# GSM.net
KiCad netlist of a schematic drawn in Altium Designer
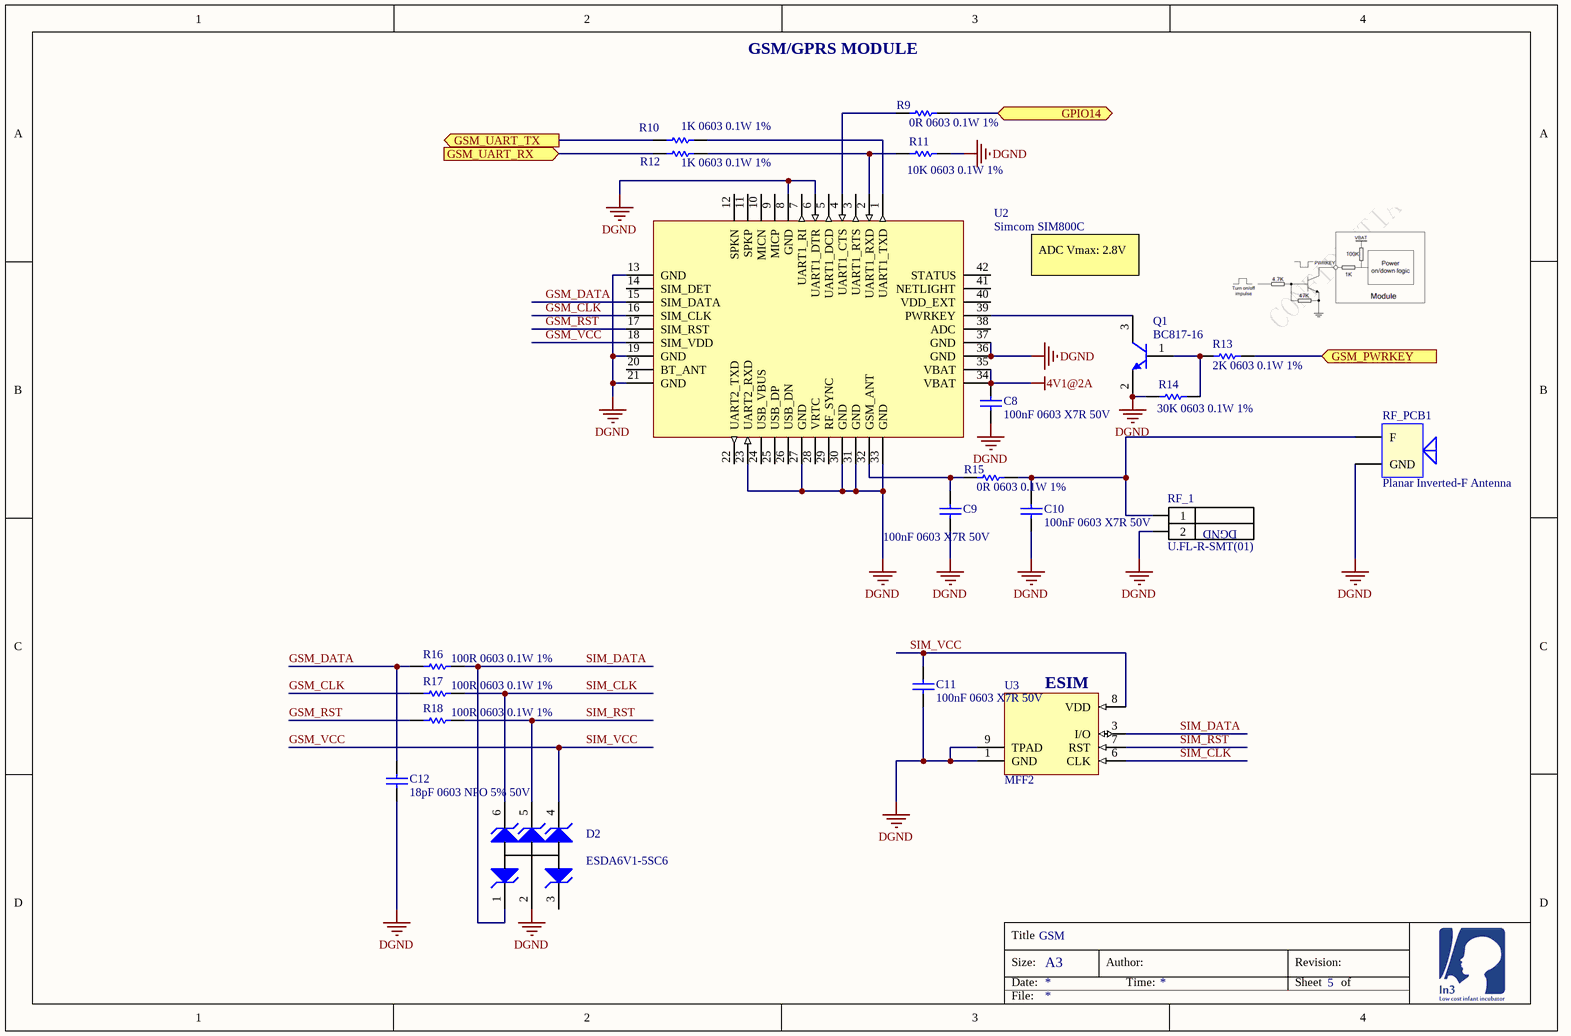
[diagram p0: GSM.SchDoc]

(export (version "E")
  (design (tool "Eeschema 10.0.6"))
  (components
    (comp (ref "C8")
      (value "100nF 0603 X7R 50V")
      (footprint "CAPC1608X60X35NL10T15")
      (description "100nF 0603 X7R 25V")
      (libsource (lib "CommunityVault") (part "CMP-c41a0d2b65641bdd-3"))
    )
    (comp (ref "C9")
      (value "100nF 0603 X7R 50V")
      (footprint "CAPC1608X60X35NL10T15")
      (description "100nF 0603 X7R 25V")
      (libsource (lib "CommunityVault") (part "CMP-c41a0d2b65641bdd-3"))
    )
    (comp (ref "C10")
      (value "100nF 0603 X7R 50V")
      (footprint "CAPC1608X60X35NL10T15")
      (description "100nF 0603 X7R 25V")
      (libsource (lib "CommunityVault") (part "CMP-c41a0d2b65641bdd-3"))
    )
    (comp (ref "C11")
      (value "100nF 0603 X7R 50V")
      (footprint "CAPC1608X60X35NL10T15")
      (description "100nF 0603 X7R 25V")
      (libsource (lib "CommunityVault") (part "CMP-c41a0d2b65641bdd-3"))
    )
    (comp (ref "C12")
      (value "18pF 0603 NPO 5% 50V")
      (footprint "CAPC1608X60X35NL10T15")
      (fields (field (name "MANUFACTURER PART NUMBER") "C0603C180K5RACTU"))
      (libsource (lib "CommunityVault") (part "CMP-35cbf9f8b0acea0c-1"))
    )
    (comp (ref "D2")
      (value "ESDA6V1-5SC6")
      (footprint "MF06A_N")
      (description "ESDA Series 5 Channel 6.1 V 50 pF SMT Uni Directional Transil Array - SOT-23-6L")
      (libsource (lib "CommunityVault") (part "CMP-924f5b40f9684d88-1"))
    )
    (comp (ref "Q1")
      (value "BC817-16")
      (footprint "PCB-856332-1")
      (description "TRANS NPN 45V 500mA SMD SOT23-3")
      (libsource (lib "CommunityVault") (part "CMP-856332-3"))
    )
    (comp (ref "R9")
      (value "0R 0603 0.1W 1%")
      (footprint "RESC1609X55X30ML10T20")
      (libsource (lib "CommunityVault") (part "CMP-536b9a7387ce8cac-10"))
    )
    (comp (ref "R10")
      (value "1K 0603 0.1W 1%")
      (footprint "RESC1609X55X30ML10T20")
      (fields (field (name "MANUFACTURER PART NUMBER") "CR0603-FX-1001ELF"))
      (libsource (lib "CommunityVault") (part "CMP-a61f6f36030f79d8-4"))
    )
    (comp (ref "R11")
      (value "10K 0603 0.1W 1%")
      (footprint "RESC1609X55X30ML10T20")
      (fields (field (name "TOLERANCE") "1%"))
      (libsource (lib "CommunityVault") (part "CMP-4716590-9"))
    )
    (comp (ref "R12")
      (value "1K 0603 0.1W 1%")
      (footprint "RESC1609X55X30ML10T20")
      (fields (field (name "MANUFACTURER PART NUMBER") "CR0603-FX-1001ELF"))
      (libsource (lib "CommunityVault") (part "CMP-a61f6f36030f79d8-4"))
    )
    (comp (ref "R13")
      (value "2K 0603 0.1W 1%")
      (footprint "RESC1609X55X30ML10T20")
      (fields (field (name "TOLERANCE") "1%"))
      (libsource (lib "CommunityVault") (part "CMP-3655986-6"))
    )
    (comp (ref "R14")
      (value "30K 0603 0.1W 1%")
      (footprint "RESC1609X55X30ML10T20")
      (fields (field (name "TOLERANCE") "1%"))
      (libsource (lib "CommunityVault") (part "CMP-3655986-6"))
    )
    (comp (ref "R15")
      (value "0R 0603 0.1W 1%")
      (footprint "RESC1609X55X30ML10T20")
      (libsource (lib "CommunityVault") (part "CMP-536b9a7387ce8cac-10"))
    )
    (comp (ref "R16")
      (value "100R 0603 0.1W 1%")
      (footprint "RESC1609X55X30ML10T20")
      (fields (field (name "MANUFACTURER PART NUMBER") "CR0603-FX-1001ELF"))
      (libsource (lib "CommunityVault") (part "CMP-a61f6f36030f79d8-4"))
    )
    (comp (ref "R17")
      (value "100R 0603 0.1W 1%")
      (footprint "RESC1609X55X30ML10T20")
      (fields (field (name "MANUFACTURER PART NUMBER") "CR0603-FX-1001ELF"))
      (libsource (lib "CommunityVault") (part "CMP-a61f6f36030f79d8-4"))
    )
    (comp (ref "R18")
      (value "100R 0603 0.1W 1%")
      (footprint "RESC1609X55X30ML10T20")
      (fields (field (name "MANUFACTURER PART NUMBER") "CR0603-FX-1001ELF"))
      (libsource (lib "CommunityVault") (part "CMP-a61f6f36030f79d8-4"))
    )
    (comp (ref "RF_1")
      (value "U.FL-R-SMT(01)")
      (footprint "PCB-ci0d6ius1xp1vci7q9ug-1")
      (description "Connector RF Coaxial Data Midget Coaxial")
      (libsource (lib "CommunityVault") (part "CMP-b06f7b3edcee6fa8-4"))
    )
    (comp (ref "RF_PCB1")
      (value "Planar Inverted-F Antenna")
      (footprint "PCB-exfs4yavada8317p37z6-1")
      (description "GSM900 and GSM1800  Frequency Bands PCB antenna")
      (libsource (lib "CommunityVault") (part "CMP-e704afk8c25r4a5ypw1c-3"))
    )
    (comp (ref "U2")
      (value "Simcom SIM800C")
      (footprint "SIM800C")
      (description "Module: GSM/Bluetooth; GPRS; 2G; 1800MHz, 900MHz; 85.6kbps; SMD")
      (fields (field (name "MANUFACTURER PART NUMBER") "SIM800C"))
      (libsource (lib "FavoritesLibrary") (part "SYM-72dbb8ea0133ad1c-1"))
    )
    (comp (ref "U3")
      (value "MFF2")
      (footprint "SON127P600X95_HS-9N")
      (description "Embedded SIM card in MFF2")
      (libsource (lib "CommunityVault") (part "CMP-ce8f06c57f401148-2"))
    )
  )
  (nets
    (net (code "1") (name "/GPIO14") (class "Default")
      (node (ref "R9") (pin "2") (pinfunction "2_2") (pintype "passive"))
    )
    (net (code "2") (name "/GSM_CLK") (class "Default")
      (node (ref "R17") (pin "2") (pinfunction "2_2") (pintype "passive"))
      (node (ref "U2") (pin "16") (pinfunction "SIM_CLK_16") (pintype "passive"))
    )
    (net (code "3") (name "/GSM_DATA") (class "Default")
      (node (ref "C12") (pin "2") (pinfunction "2_2") (pintype "passive"))
      (node (ref "R16") (pin "2") (pinfunction "2_2") (pintype "passive"))
      (node (ref "U2") (pin "15") (pinfunction "SIM_DATA_15") (pintype "passive"))
    )
    (net (code "4") (name "/GSM_PWRKEY") (class "Default")
      (node (ref "R13") (pin "1") (pinfunction "1_1") (pintype "passive"))
    )
    (net (code "5") (name "/GSM_RST") (class "Default")
      (node (ref "R18") (pin "2") (pinfunction "2_2") (pintype "passive"))
      (node (ref "U2") (pin "17") (pinfunction "SIM_RST_17") (pintype "passive"))
    )
    (net (code "6") (name "/GSM_UART_RX") (class "Default")
      (node (ref "R12") (pin "1") (pinfunction "1_1") (pintype "passive"))
    )
    (net (code "7") (name "/GSM_UART_TX") (class "Default")
      (node (ref "R10") (pin "1") (pinfunction "1_1") (pintype "passive"))
    )
    (net (code "8") (name "/GSM_VCC") (class "Default")
      (node (ref "C11") (pin "2") (pinfunction "2_2") (pintype "passive"))
      (node (ref "D2") (pin "4") (pinfunction "A_4") (pintype "passive"))
      (node (ref "U2") (pin "18") (pinfunction "SIM_VDD_18") (pintype "passive"))
      (node (ref "U3") (pin "8") (pinfunction "VDD_8") (pintype "input"))
    )
    (net (code "9") (name "/SIM_CLK") (class "Default")
      (node (ref "D2") (pin "6") (pinfunction "A_6") (pintype "passive"))
      (node (ref "R17") (pin "1") (pinfunction "1_1") (pintype "passive"))
      (node (ref "U3") (pin "6") (pinfunction "CLK_6") (pintype "input"))
    )
    (net (code "10") (name "/SIM_DATA") (class "Default")
      (node (ref "D2") (pin "1") (pinfunction "K_1") (pintype "passive"))
      (node (ref "R16") (pin "1") (pinfunction "1_1") (pintype "passive"))
      (node (ref "U3") (pin "3") (pinfunction "I/O_3") (pintype "bidirectional"))
    )
    (net (code "11") (name "/SIM_RST") (class "Default")
      (node (ref "D2") (pin "5") (pinfunction "A_5") (pintype "passive"))
      (node (ref "R18") (pin "1") (pinfunction "1_1") (pintype "passive"))
      (node (ref "U3") (pin "7") (pinfunction "RST_7") (pintype "input"))
    )
    (net (code "12") (name "4V1@2A") (class "Default")
      (node (ref "C8") (pin "2") (pinfunction "2_2") (pintype "passive"))
      (node (ref "U2") (pin "34") (pinfunction "VBAT_34") (pintype "passive"))
      (node (ref "U2") (pin "35") (pinfunction "VBAT_35") (pintype "passive"))
    )
    (net (code "13") (name "DGND") (class "Default")
      (node (ref "C10") (pin "1") (pinfunction "1_1") (pintype "passive"))
      (node (ref "C11") (pin "1") (pinfunction "1_1") (pintype "passive"))
      (node (ref "C12") (pin "1") (pinfunction "1_1") (pintype "passive"))
      (node (ref "C8") (pin "1") (pinfunction "1_1") (pintype "passive"))
      (node (ref "C9") (pin "1") (pinfunction "1_1") (pintype "passive"))
      (node (ref "D2") (pin "2") (pinfunction "K_2") (pintype "passive"))
      (node (ref "Q1") (pin "2") (pinfunction "E_2") (pintype "passive"))
      (node (ref "R11") (pin "2") (pinfunction "2_2") (pintype "passive"))
      (node (ref "R14") (pin "2") (pinfunction "2_2") (pintype "passive"))
      (node (ref "RF_1") (pin "2") (pinfunction "2_2") (pintype "passive"))
      (node (ref "RF_PCB1") (pin "2") (pinfunction "GND_2") (pintype "passive"))
      (node (ref "U2") (pin "13") (pinfunction "GND_13") (pintype "passive"))
      (node (ref "U2") (pin "19") (pinfunction "GND_19") (pintype "passive"))
      (node (ref "U2") (pin "21") (pinfunction "GND_21") (pintype "passive"))
      (node (ref "U2") (pin "23") (pinfunction "UART2_RXD_23") (pintype "input"))
      (node (ref "U2") (pin "27") (pinfunction "GND_27") (pintype "power_in"))
      (node (ref "U2") (pin "30") (pinfunction "GND_30") (pintype "power_in"))
      (node (ref "U2") (pin "31") (pinfunction "GND_31") (pintype "power_in"))
      (node (ref "U2") (pin "33") (pinfunction "GND_33") (pintype "power_in"))
      (node (ref "U2") (pin "36") (pinfunction "GND_36") (pintype "power_in"))
      (node (ref "U2") (pin "37") (pinfunction "GND_37") (pintype "power_in"))
      (node (ref "U2") (pin "6") (pinfunction "UART1_DTR_6") (pintype "input"))
      (node (ref "U2") (pin "8") (pinfunction "GND_8") (pintype "power_in"))
      (node (ref "U3") (pin "1") (pinfunction "GND_1") (pintype "power_in"))
      (node (ref "U3") (pin "9") (pinfunction "TPAD_9") (pintype "power_in"))
    )
    (net (code "14") (name "Net-(Q1-B)") (class "Default")
      (node (ref "Q1") (pin "1") (pinfunction "B_1") (pintype "passive"))
      (node (ref "R13") (pin "2") (pinfunction "2_2") (pintype "passive"))
      (node (ref "R14") (pin "1") (pinfunction "1_1") (pintype "passive"))
    )
    (net (code "15") (name "Net-(Q1-C)") (class "Default")
      (node (ref "Q1") (pin "3") (pinfunction "C_3") (pintype "passive"))
      (node (ref "U2") (pin "39") (pinfunction "PWRKEY_39") (pintype "passive"))
    )
    (net (code "16") (name "Net-(RF_PCB1-F)") (class "Default")
      (node (ref "C10") (pin "2") (pinfunction "2_2") (pintype "passive"))
      (node (ref "R15") (pin "2") (pinfunction "2_2") (pintype "passive"))
      (node (ref "RF_1") (pin "1") (pinfunction "1_1") (pintype "passive"))
      (node (ref "RF_PCB1") (pin "1") (pinfunction "F_1") (pintype "passive"))
    )
    (net (code "17") (name "Net-(U2-GSM_ANT)") (class "Default")
      (node (ref "C9") (pin "2") (pinfunction "2_2") (pintype "passive"))
      (node (ref "R15") (pin "1") (pinfunction "1_1") (pintype "passive"))
      (node (ref "U2") (pin "32") (pinfunction "GSM_ANT_32") (pintype "passive"))
    )
    (net (code "18") (name "Net-(U2-UART1_CTS)") (class "Default")
      (node (ref "R9") (pin "1") (pinfunction "1_1") (pintype "passive"))
      (node (ref "U2") (pin "4") (pinfunction "UART1_CTS_4") (pintype "input"))
    )
    (net (code "19") (name "Net-(U2-UART1_RXD)") (class "Default")
      (node (ref "R11") (pin "1") (pinfunction "1_1") (pintype "passive"))
      (node (ref "R12") (pin "2") (pinfunction "2_2") (pintype "passive"))
      (node (ref "U2") (pin "2") (pinfunction "UART1_RXD_2") (pintype "input"))
    )
    (net (code "20") (name "Net-(U2-UART1_TXD)") (class "Default")
      (node (ref "R10") (pin "2") (pinfunction "2_2") (pintype "passive"))
      (node (ref "U2") (pin "1") (pinfunction "UART1_TXD_1") (pintype "output"))
    )
    (net (code "21") (name "unconnected-(D2-K-Pad3)") (class "Default")
      (node (ref "D2") (pin "3") (pinfunction "K_3") (pintype "passive"))
    )
    (net (code "22") (name "unconnected-(U2-ADC-Pad38)") (class "Default")
      (node (ref "U2") (pin "38") (pinfunction "ADC_38") (pintype "passive"))
    )
    (net (code "23") (name "unconnected-(U2-BT_ANT-Pad20)") (class "Default")
      (node (ref "U2") (pin "20") (pinfunction "BT_ANT_20") (pintype "passive"))
    )
    (net (code "24") (name "unconnected-(U2-MICN-Pad10)") (class "Default")
      (node (ref "U2") (pin "10") (pinfunction "MICN_10") (pintype "passive"))
    )
    (net (code "25") (name "unconnected-(U2-MICP-Pad9)") (class "Default")
      (node (ref "U2") (pin "9") (pinfunction "MICP_9") (pintype "passive"))
    )
    (net (code "26") (name "unconnected-(U2-NETLIGHT-Pad41)") (class "Default")
      (node (ref "U2") (pin "41") (pinfunction "NETLIGHT_41") (pintype "passive"))
    )
    (net (code "27") (name "unconnected-(U2-RF_SYNC-Pad29)") (class "Default")
      (node (ref "U2") (pin "29") (pinfunction "RF_SYNC_29") (pintype "passive"))
    )
    (net (code "28") (name "unconnected-(U2-SIM_DET-Pad14)") (class "Default")
      (node (ref "U2") (pin "14") (pinfunction "SIM_DET_14") (pintype "passive"))
    )
    (net (code "29") (name "unconnected-(U2-SPKN-Pad12)") (class "Default")
      (node (ref "U2") (pin "12") (pinfunction "SPKN_12") (pintype "passive"))
    )
    (net (code "30") (name "unconnected-(U2-SPKP-Pad11)") (class "Default")
      (node (ref "U2") (pin "11") (pinfunction "SPKP_11") (pintype "passive"))
    )
    (net (code "31") (name "unconnected-(U2-STATUS-Pad42)") (class "Default")
      (node (ref "U2") (pin "42") (pinfunction "STATUS_42") (pintype "passive"))
    )
    (net (code "32") (name "unconnected-(U2-UART1_DCD-Pad5)") (class "Default")
      (node (ref "U2") (pin "5") (pinfunction "UART1_DCD_5") (pintype "output"))
    )
    (net (code "33") (name "unconnected-(U2-UART1_RI-Pad7)") (class "Default")
      (node (ref "U2") (pin "7") (pinfunction "UART1_RI_7") (pintype "output"))
    )
    (net (code "34") (name "unconnected-(U2-UART1_RTS-Pad3)") (class "Default")
      (node (ref "U2") (pin "3") (pinfunction "UART1_RTS_3") (pintype "output"))
    )
    (net (code "35") (name "unconnected-(U2-UART2_TXD-Pad22)") (class "Default")
      (node (ref "U2") (pin "22") (pinfunction "UART2_TXD_22") (pintype "output"))
    )
    (net (code "36") (name "unconnected-(U2-USB_DN-Pad26)") (class "Default")
      (node (ref "U2") (pin "26") (pinfunction "USB_DN_26") (pintype "passive"))
    )
    (net (code "37") (name "unconnected-(U2-USB_DP-Pad25)") (class "Default")
      (node (ref "U2") (pin "25") (pinfunction "USB_DP_25") (pintype "passive"))
    )
    (net (code "38") (name "unconnected-(U2-USB_VBUS-Pad24)") (class "Default")
      (node (ref "U2") (pin "24") (pinfunction "USB_VBUS_24") (pintype "passive"))
    )
    (net (code "39") (name "unconnected-(U2-VDD_EXT-Pad40)") (class "Default")
      (node (ref "U2") (pin "40") (pinfunction "VDD_EXT_40") (pintype "passive"))
    )
    (net (code "40") (name "unconnected-(U2-VRTC-Pad28)") (class "Default")
      (node (ref "U2") (pin "28") (pinfunction "VRTC_28") (pintype "passive"))
    )
  )
)
